# schematic_full.net
KiCad netlist of a schematic drawn in EAGLE
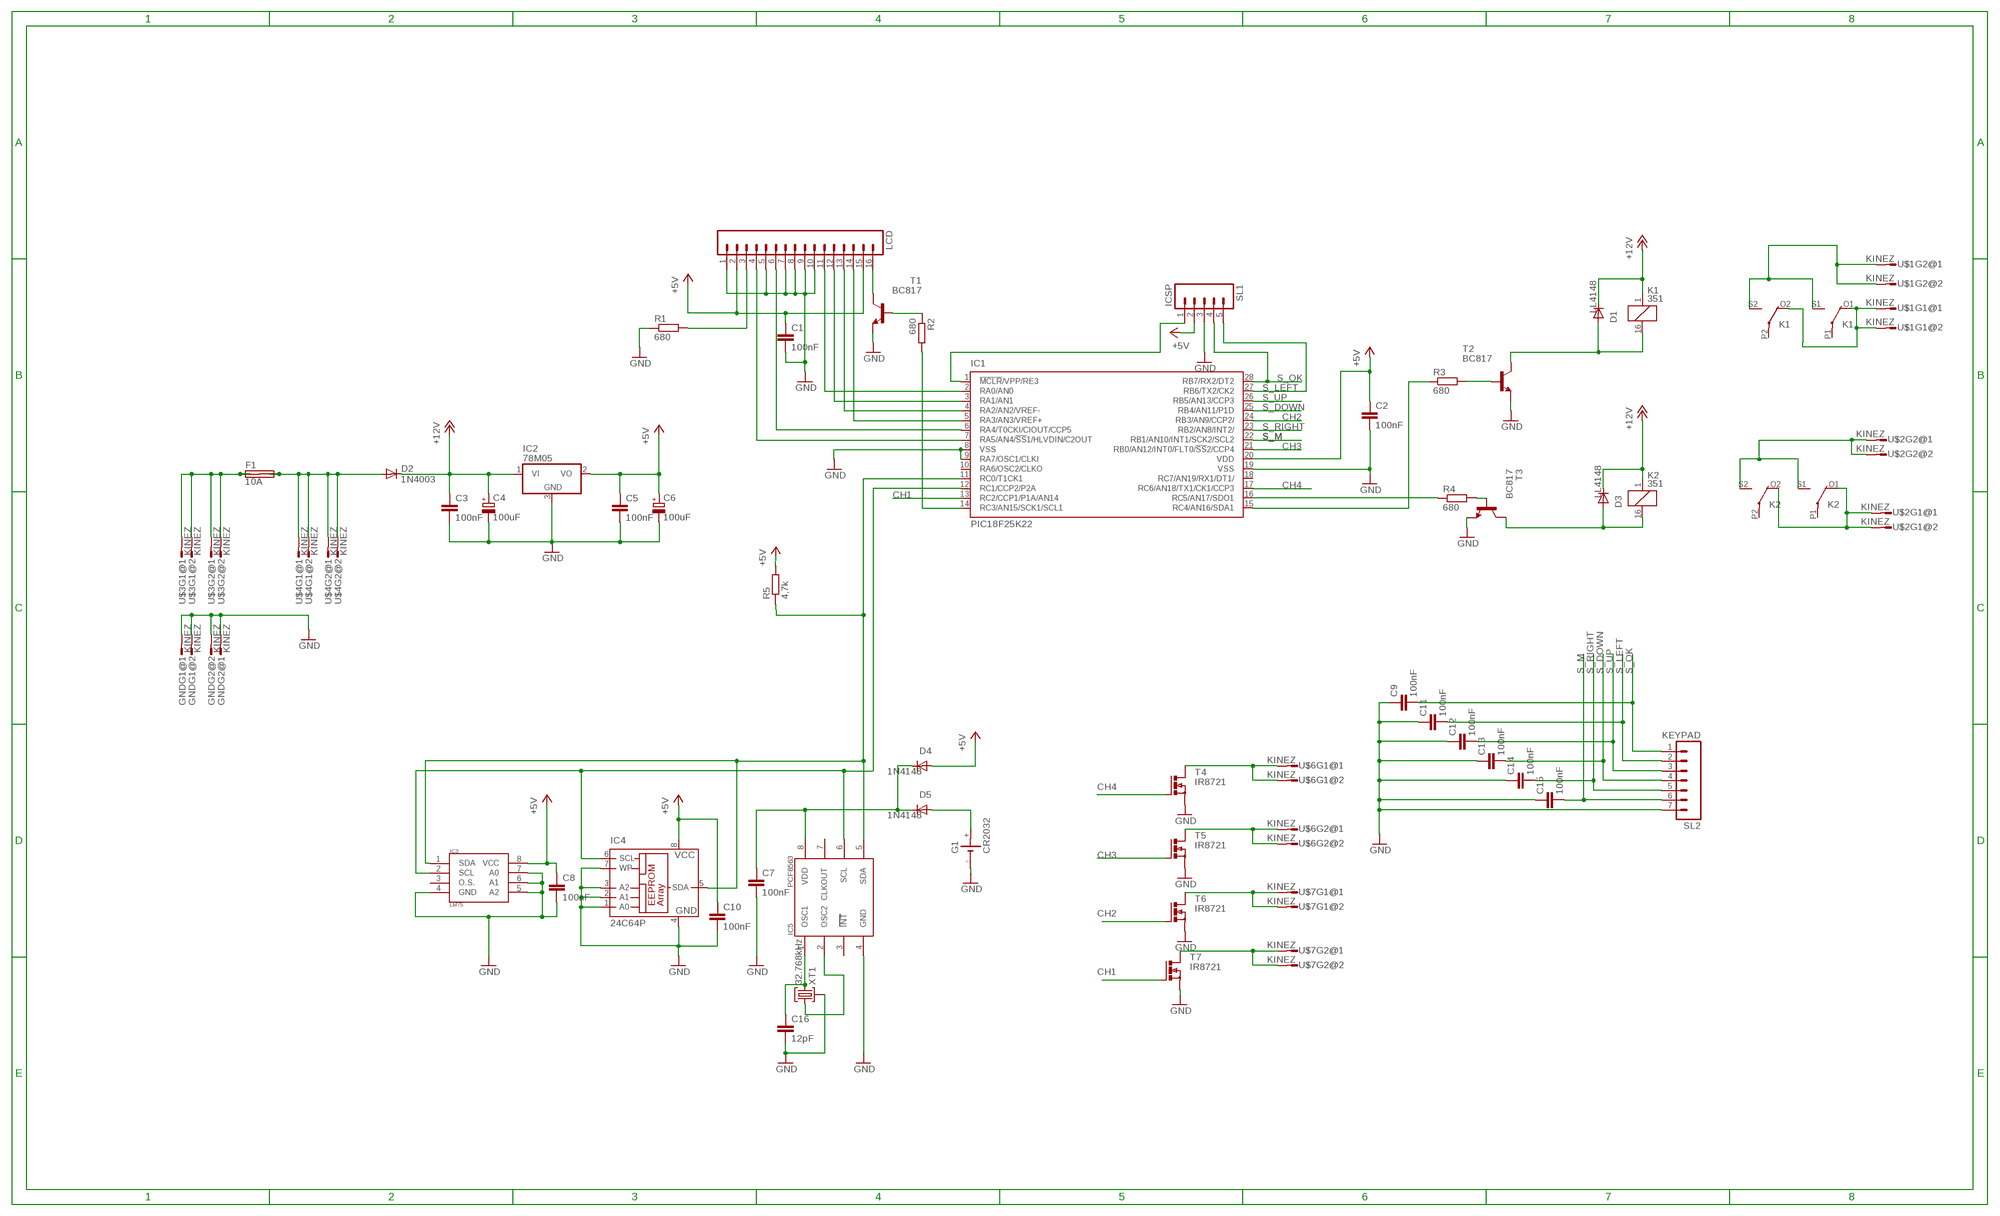
[diagram p0: schematic, sheet 1]

(export (version "E")
  (design (tool "Eeschema 10.0.6"))
  (components
    (comp (ref "C1")
      (value "100nF")
      (footprint "eagle-import:C0805K")
      (libsource (lib "eagle-import") (part "C-EUC0805K"))
    )
    (comp (ref "C2")
      (value "100nF")
      (footprint "eagle-import:C0805K")
      (libsource (lib "eagle-import") (part "C-EUC0805K"))
    )
    (comp (ref "C3")
      (value "100nF")
      (footprint "eagle-import:C0805K")
      (libsource (lib "eagle-import") (part "C-EUC0805K"))
    )
    (comp (ref "C4")
      (value "100uF")
      (footprint "eagle-import:E2,5-6E")
      (libsource (lib "eagle-import") (part "CPOL-EUE2,5-6E"))
    )
    (comp (ref "C5")
      (value "100nF")
      (footprint "eagle-import:C0805K")
      (libsource (lib "eagle-import") (part "C-EUC0805K"))
    )
    (comp (ref "C6")
      (value "100uF")
      (footprint "eagle-import:E2,5-6")
      (libsource (lib "eagle-import") (part "CPOL-EUE2.5-6"))
    )
    (comp (ref "C7")
      (value "100nF")
      (footprint "eagle-import:C0805K")
      (libsource (lib "eagle-import") (part "C-EUC0805K"))
    )
    (comp (ref "C8")
      (value "100nF")
      (footprint "eagle-import:C0805K")
      (libsource (lib "eagle-import") (part "C-EUC0805K"))
    )
    (comp (ref "C9")
      (value "100nF")
      (footprint "eagle-import:C0805K")
      (libsource (lib "eagle-import") (part "C-EUC0805K"))
    )
    (comp (ref "C10")
      (value "100nF")
      (footprint "eagle-import:C0805K")
      (libsource (lib "eagle-import") (part "C-EUC0805K"))
    )
    (comp (ref "C11")
      (value "100nF")
      (footprint "eagle-import:C0805K")
      (libsource (lib "eagle-import") (part "C-EUC0805K"))
    )
    (comp (ref "C12")
      (value "100nF")
      (footprint "eagle-import:C0805K")
      (libsource (lib "eagle-import") (part "C-EUC0805K"))
    )
    (comp (ref "C13")
      (value "100nF")
      (footprint "eagle-import:C0805K")
      (libsource (lib "eagle-import") (part "C-EUC0805K"))
    )
    (comp (ref "C14")
      (value "100nF")
      (footprint "eagle-import:C0805K")
      (libsource (lib "eagle-import") (part "C-EUC0805K"))
    )
    (comp (ref "C15")
      (value "100nF")
      (footprint "eagle-import:C0805K")
      (libsource (lib "eagle-import") (part "C-EUC0805K"))
    )
    (comp (ref "C16")
      (value "12pF")
      (footprint "eagle-import:C0805K")
      (libsource (lib "eagle-import") (part "C-EUC0805K"))
    )
    (comp (ref "D1")
      (value "LL4148")
      (footprint "eagle-import:DO214BA")
      (libsource (lib "eagle-import") (part "DIODE-DO214BA"))
    )
    (comp (ref "D2")
      (value "1N4003")
      (footprint "eagle-import:DO41-10")
      (libsource (lib "eagle-import") (part "1N4933"))
    )
    (comp (ref "D3")
      (value "LL4148")
      (footprint "eagle-import:DO214BA")
      (libsource (lib "eagle-import") (part "DIODE-DO214BA"))
    )
    (comp (ref "D4")
      (value "1N4148")
      (footprint "eagle-import:DO214BA")
      (libsource (lib "eagle-import") (part "DIODE-DO214BA"))
    )
    (comp (ref "D5")
      (value "1N4148")
      (footprint "eagle-import:DO214BA")
      (libsource (lib "eagle-import") (part "DIODE-DO214BA"))
    )
    (comp (ref "F1")
      (value "10A")
      (footprint "eagle-import:SHK20L")
      (libsource (lib "eagle-import") (part "SHK20L"))
    )
    (comp (ref "G1")
      (value "CR2032")
      (footprint "eagle-import:CR2032")
      (libsource (lib "eagle-import") (part "CR2032"))
    )
    (comp (ref "GND")
      (value "KINEZ")
      (footprint "eagle-import:KINEZ")
      (libsource (lib "eagle-import") (part "KINEZ"))
    )
    (comp (ref "IC1")
      (value "PIC18F25K22")
      (footprint "eagle-import:SSOP28")
      (libsource (lib "eagle-import") (part "PIC18F25K22/SS-E"))
    )
    (comp (ref "IC2")
      (value "78M05")
      (footprint "eagle-import:TO252")
      (libsource (lib "eagle-import") (part "78DT05"))
    )
    (comp (ref "IC3")
      (value "LM75")
      (footprint "eagle-import:SO08")
      (libsource (lib "eagle-import") (part "LM75"))
    )
    (comp (ref "IC4")
      (value "24C64P")
      (footprint "eagle-import:DIL8")
      (libsource (lib "eagle-import") (part "24PC64"))
    )
    (comp (ref "IC5")
      (value "PCF8563")
      (footprint "eagle-import:SO08")
      (libsource (lib "eagle-import") (part "PCF8563"))
    )
    (comp (ref "K1")
      (value "351")
      (footprint "eagle-import:351")
      (libsource (lib "eagle-import") (part "351"))
    )
    (comp (ref "K2")
      (value "351")
      (footprint "eagle-import:351")
      (libsource (lib "eagle-import") (part "351"))
    )
    (comp (ref "LCD")
      (value "M16")
      (footprint "eagle-import:16P")
      (libsource (lib "eagle-import") (part "M16"))
    )
    (comp (ref "R1")
      (value "680")
      (footprint "eagle-import:M0805")
      (libsource (lib "eagle-import") (part "R-EU_M0805"))
    )
    (comp (ref "R2")
      (value "680")
      (footprint "eagle-import:M0805")
      (libsource (lib "eagle-import") (part "R-EU_M0805"))
    )
    (comp (ref "R3")
      (value "680")
      (footprint "eagle-import:M0805")
      (libsource (lib "eagle-import") (part "R-EU_M0805"))
    )
    (comp (ref "R4")
      (value "680")
      (footprint "eagle-import:M0805")
      (libsource (lib "eagle-import") (part "R-EU_M0805"))
    )
    (comp (ref "R5")
      (value "4,7k")
      (footprint "eagle-import:M0805")
      (libsource (lib "eagle-import") (part "R-EU_M0805"))
    )
    (comp (ref "SL1")
      (value "ICSP")
      (footprint "eagle-import:05P")
      (libsource (lib "eagle-import") (part "M05"))
    )
    (comp (ref "SL2")
      (value "KEYPAD")
      (footprint "eagle-import:07PA")
      (libsource (lib "eagle-import") (part "MA07"))
    )
    (comp (ref "T1")
      (value "BC817")
      (footprint "eagle-import:SOT23-BEC")
      (libsource (lib "eagle-import") (part "BC817SMD-40"))
    )
    (comp (ref "T2")
      (value "BC817")
      (footprint "eagle-import:SOT23-BEC")
      (libsource (lib "eagle-import") (part "BC817SMD-40"))
    )
    (comp (ref "T3")
      (value "BC817")
      (footprint "eagle-import:SOT23-BEC")
      (libsource (lib "eagle-import") (part "BC817SMD-40"))
    )
    (comp (ref "T4")
      (value "IR8721")
      (footprint "eagle-import:TO252")
      (libsource (lib "eagle-import") (part "IRLR120N"))
    )
    (comp (ref "T5")
      (value "IR8721")
      (footprint "eagle-import:TO252")
      (libsource (lib "eagle-import") (part "IRLR120N"))
    )
    (comp (ref "T6")
      (value "IR8721")
      (footprint "eagle-import:TO252")
      (libsource (lib "eagle-import") (part "IRLR120N"))
    )
    (comp (ref "T7")
      (value "IR8721")
      (footprint "eagle-import:TO252")
      (libsource (lib "eagle-import") (part "IRLR120N"))
    )
    (comp (ref "U$1")
      (value "KINEZ")
      (footprint "eagle-import:KINEZ")
      (libsource (lib "eagle-import") (part "KINEZ"))
    )
    (comp (ref "U$2")
      (value "KINEZ")
      (footprint "eagle-import:KINEZ")
      (libsource (lib "eagle-import") (part "KINEZ"))
    )
    (comp (ref "U$3")
      (value "KINEZ")
      (footprint "eagle-import:KINEZ")
      (libsource (lib "eagle-import") (part "KINEZ"))
    )
    (comp (ref "U$4")
      (value "KINEZ")
      (footprint "eagle-import:KINEZ")
      (libsource (lib "eagle-import") (part "KINEZ"))
    )
    (comp (ref "U$6")
      (value "KINEZ")
      (footprint "eagle-import:KINEZ")
      (libsource (lib "eagle-import") (part "KINEZ"))
    )
    (comp (ref "U$7")
      (value "KINEZ")
      (footprint "eagle-import:KINEZ")
      (libsource (lib "eagle-import") (part "KINEZ"))
    )
    (comp (ref "XT1")
      (value "32.768kHz")
      (footprint "eagle-import:XTMINI")
      (libsource (lib "eagle-import") (part "XTMINI"))
    )
  )
  (nets
    (net (code "1") (name "+5V") (class "Default")
      (node (ref "C1") (pin "1") (pinfunction "1_1") (pintype "passive"))
      (node (ref "C10") (pin "1") (pinfunction "1_1") (pintype "passive"))
      (node (ref "C2") (pin "1") (pinfunction "1_1") (pintype "passive"))
      (node (ref "C5") (pin "1") (pinfunction "1_1") (pintype "passive"))
      (node (ref "C6") (pin "+") (pinfunction "+_+") (pintype "passive"))
      (node (ref "C8") (pin "1") (pinfunction "1_1") (pintype "passive"))
      (node (ref "D4") (pin "A") (pinfunction "A_A") (pintype "passive"))
      (node (ref "IC1") (pin "20") (pinfunction "VDD_20") (pintype "power_in"))
      (node (ref "IC2") (pin "2") (pinfunction "VO_2") (pintype "passive"))
      (node (ref "IC3") (pin "8") (pinfunction "VCC_8") (pintype "bidirectional"))
      (node (ref "IC4") (pin "8") (pinfunction "VCC_8") (pintype "power_in"))
      (node (ref "LCD") (pin "15") (pinfunction "15_15") (pintype "passive"))
      (node (ref "LCD") (pin "2") (pinfunction "2_2") (pintype "passive"))
      (node (ref "R5") (pin "2") (pinfunction "2_2") (pintype "passive"))
      (node (ref "SL1") (pin "2") (pinfunction "2_2") (pintype "passive"))
    )
    (net (code "2") (name "+12V") (class "Default")
      (node (ref "C3") (pin "1") (pinfunction "1_1") (pintype "passive"))
      (node (ref "C4") (pin "+") (pinfunction "+_+") (pintype "passive"))
      (node (ref "D1") (pin "C") (pinfunction "C_C") (pintype "passive"))
      (node (ref "D2") (pin "C") (pinfunction "C_C") (pintype "passive"))
      (node (ref "D3") (pin "C") (pinfunction "C_C") (pintype "passive"))
      (node (ref "IC2") (pin "1") (pinfunction "VI_1") (pintype "input"))
      (node (ref "K1") (pin "1") (pinfunction "1_1") (pintype "passive"))
      (node (ref "K2") (pin "1") (pinfunction "1_1") (pintype "passive"))
    )
    (net (code "3") (name "/CH1") (class "Default")
      (node (ref "IC1") (pin "13") (pinfunction "RC2/CCP1/P1A/AN14_13") (pintype "bidirectional"))
      (node (ref "T7") (pin "1") (pinfunction "G_1") (pintype "passive"))
    )
    (net (code "4") (name "/CH2") (class "Default")
      (node (ref "IC1") (pin "24") (pinfunction "RB3/AN9/CCP2/_24") (pintype "bidirectional"))
      (node (ref "T6") (pin "1") (pinfunction "G_1") (pintype "passive"))
    )
    (net (code "5") (name "/CH3") (class "Default")
      (node (ref "IC1") (pin "21") (pinfunction "RB0/AN12/INT0/FLT0/~{SS}2/CCP4_21") (pintype "bidirectional"))
      (node (ref "T5") (pin "1") (pinfunction "G_1") (pintype "passive"))
    )
    (net (code "6") (name "/CH4") (class "Default")
      (node (ref "IC1") (pin "17") (pinfunction "RC6/AN18/TX1/CK1/CCP3_17") (pintype "bidirectional"))
      (node (ref "T4") (pin "1") (pinfunction "G_1") (pintype "passive"))
    )
    (net (code "7") (name "/S_DOWN") (class "Default")
      (node (ref "C13") (pin "2") (pinfunction "2_2") (pintype "passive"))
      (node (ref "IC1") (pin "25") (pinfunction "RB4/AN11/P1D_25") (pintype "bidirectional"))
      (node (ref "SL2") (pin "4") (pinfunction "4_4") (pintype "passive"))
    )
    (net (code "8") (name "/S_LEFT") (class "Default")
      (node (ref "C11") (pin "2") (pinfunction "2_2") (pintype "passive"))
      (node (ref "IC1") (pin "27") (pinfunction "RB6/TX2/CK2_27") (pintype "bidirectional"))
      (node (ref "SL1") (pin "5") (pinfunction "5_5") (pintype "passive"))
      (node (ref "SL2") (pin "2") (pinfunction "2_2") (pintype "passive"))
    )
    (net (code "9") (name "/S_M") (class "Default")
      (node (ref "C15") (pin "2") (pinfunction "2_2") (pintype "passive"))
      (node (ref "IC1") (pin "22") (pinfunction "RB1/AN10/INT1/SCK2/SCL2_22") (pintype "bidirectional"))
      (node (ref "SL2") (pin "6") (pinfunction "6_6") (pintype "passive"))
    )
    (net (code "10") (name "/S_OK") (class "Default")
      (node (ref "C9") (pin "2") (pinfunction "2_2") (pintype "passive"))
      (node (ref "IC1") (pin "28") (pinfunction "RB7/RX2/DT2_28") (pintype "bidirectional"))
      (node (ref "SL1") (pin "4") (pinfunction "4_4") (pintype "passive"))
      (node (ref "SL2") (pin "1") (pinfunction "1_1") (pintype "passive"))
    )
    (net (code "11") (name "/S_RIGHT") (class "Default")
      (node (ref "C14") (pin "2") (pinfunction "2_2") (pintype "passive"))
      (node (ref "IC1") (pin "23") (pinfunction "RB2/AN8/INT2/_23") (pintype "bidirectional"))
      (node (ref "SL2") (pin "5") (pinfunction "5_5") (pintype "passive"))
    )
    (net (code "12") (name "/S_UP") (class "Default")
      (node (ref "C12") (pin "2") (pinfunction "2_2") (pintype "passive"))
      (node (ref "IC1") (pin "26") (pinfunction "RB5/AN13/CCP3_26") (pintype "bidirectional"))
      (node (ref "SL2") (pin "3") (pinfunction "3_3") (pintype "passive"))
    )
    (net (code "13") (name "GND") (class "Default")
      (node (ref "C1") (pin "2") (pinfunction "2_2") (pintype "passive"))
      (node (ref "C10") (pin "2") (pinfunction "2_2") (pintype "passive"))
      (node (ref "C11") (pin "1") (pinfunction "1_1") (pintype "passive"))
      (node (ref "C12") (pin "1") (pinfunction "1_1") (pintype "passive"))
      (node (ref "C13") (pin "1") (pinfunction "1_1") (pintype "passive"))
      (node (ref "C14") (pin "1") (pinfunction "1_1") (pintype "passive"))
      (node (ref "C15") (pin "1") (pinfunction "1_1") (pintype "passive"))
      (node (ref "C16") (pin "2") (pinfunction "2_2") (pintype "passive"))
      (node (ref "C2") (pin "2") (pinfunction "2_2") (pintype "passive"))
      (node (ref "C3") (pin "2") (pinfunction "2_2") (pintype "passive"))
      (node (ref "C4") (pin "-") (pinfunction "-_-") (pintype "passive"))
      (node (ref "C5") (pin "2") (pinfunction "2_2") (pintype "passive"))
      (node (ref "C6") (pin "-") (pinfunction "-_-") (pintype "passive"))
      (node (ref "C7") (pin "2") (pinfunction "2_2") (pintype "passive"))
      (node (ref "C8") (pin "2") (pinfunction "2_2") (pintype "passive"))
      (node (ref "C9") (pin "1") (pinfunction "1_1") (pintype "passive"))
      (node (ref "G1") (pin "-") (pinfunction "-_-") (pintype "passive"))
      (node (ref "GND") (pin "1") (pinfunction "S_1") (pintype "passive"))
      (node (ref "GND") (pin "2") (pinfunction "S_2") (pintype "passive"))
      (node (ref "GND") (pin "3") (pinfunction "S_3") (pintype "passive"))
      (node (ref "GND") (pin "4") (pinfunction "S_4") (pintype "passive"))
      (node (ref "IC1") (pin "19") (pinfunction "VSS_19") (pintype "power_in"))
      (node (ref "IC1") (pin "8") (pinfunction "VSS_8") (pintype "power_in"))
      (node (ref "IC1") (pin "9") (pinfunction "RA7/OSC1/CLKI_9") (pintype "input"))
      (node (ref "IC2") (pin "3") (pinfunction "GND_3") (pintype "passive"))
      (node (ref "IC3") (pin "4") (pinfunction "GND_4") (pintype "bidirectional"))
      (node (ref "IC3") (pin "5") (pinfunction "A2_5") (pintype "bidirectional"))
      (node (ref "IC3") (pin "6") (pinfunction "A1_6") (pintype "bidirectional"))
      (node (ref "IC3") (pin "7") (pinfunction "A0_7") (pintype "bidirectional"))
      (node (ref "IC4") (pin "1") (pinfunction "A0_1") (pintype "input"))
      (node (ref "IC4") (pin "2") (pinfunction "A1_2") (pintype "input"))
      (node (ref "IC4") (pin "3") (pinfunction "A2_3") (pintype "input"))
      (node (ref "IC4") (pin "4") (pinfunction "GND_4") (pintype "power_in"))
      (node (ref "IC4") (pin "7") (pinfunction "WP_7") (pintype "input"))
      (node (ref "IC5") (pin "4") (pinfunction "GND_4") (pintype "bidirectional"))
      (node (ref "LCD") (pin "1") (pinfunction "1_1") (pintype "passive"))
      (node (ref "LCD") (pin "10") (pinfunction "10_10") (pintype "passive"))
      (node (ref "LCD") (pin "5") (pinfunction "5_5") (pintype "passive"))
      (node (ref "LCD") (pin "7") (pinfunction "7_7") (pintype "passive"))
      (node (ref "LCD") (pin "8") (pinfunction "8_8") (pintype "passive"))
      (node (ref "LCD") (pin "9") (pinfunction "9_9") (pintype "passive"))
      (node (ref "R1") (pin "1") (pinfunction "1_1") (pintype "passive"))
      (node (ref "SL1") (pin "3") (pinfunction "3_3") (pintype "passive"))
      (node (ref "SL2") (pin "7") (pinfunction "7_7") (pintype "passive"))
      (node (ref "T1") (pin "E") (pinfunction "E_E") (pintype "passive"))
      (node (ref "T2") (pin "E") (pinfunction "E_E") (pintype "passive"))
      (node (ref "T3") (pin "E") (pinfunction "E_E") (pintype "passive"))
      (node (ref "T4") (pin "3") (pinfunction "S_3") (pintype "passive"))
      (node (ref "T5") (pin "3") (pinfunction "S_3") (pintype "passive"))
      (node (ref "T6") (pin "3") (pinfunction "S_3") (pintype "passive"))
      (node (ref "T7") (pin "3") (pinfunction "S_3") (pintype "passive"))
      (node (ref "XT1") (pin "P$3") (pinfunction "3_P$3") (pintype "passive"))
    )
    (net (code "14") (name "Net-(D5-PadA)") (class "Default")
      (node (ref "D5") (pin "A") (pinfunction "A_A") (pintype "passive"))
      (node (ref "G1") (pin "+") (pinfunction "+_+") (pintype "passive"))
    )
    (net (code "15") (name "Net-(IC1-RA0{slash}AN0)") (class "Default")
      (node (ref "IC1") (pin "2") (pinfunction "RA0/AN0_2") (pintype "bidirectional"))
      (node (ref "LCD") (pin "11") (pinfunction "11_11") (pintype "passive"))
    )
    (net (code "16") (name "Net-(IC1-RA1{slash}AN1)") (class "Default")
      (node (ref "IC1") (pin "3") (pinfunction "RA1/AN1_3") (pintype "bidirectional"))
      (node (ref "LCD") (pin "12") (pinfunction "12_12") (pintype "passive"))
    )
    (net (code "17") (name "Net-(IC1-RA2{slash}AN2{slash}VREF-)") (class "Default")
      (node (ref "IC1") (pin "4") (pinfunction "RA2/AN2/VREF-_4") (pintype "bidirectional"))
      (node (ref "LCD") (pin "13") (pinfunction "13_13") (pintype "passive"))
    )
    (net (code "18") (name "Net-(IC1-RA3{slash}AN3{slash}VREF+)") (class "Default")
      (node (ref "IC1") (pin "5") (pinfunction "RA3/AN3/VREF+_5") (pintype "bidirectional"))
      (node (ref "LCD") (pin "14") (pinfunction "14_14") (pintype "passive"))
    )
    (net (code "19") (name "Net-(IC1-RA4{slash}T0CKI{slash}CIOUT{slash}CCP5)") (class "Default")
      (node (ref "IC1") (pin "6") (pinfunction "RA4/T0CKI/CIOUT/CCP5_6") (pintype "bidirectional"))
      (node (ref "LCD") (pin "6") (pinfunction "6_6") (pintype "passive"))
    )
    (net (code "20") (name "Net-(IC1-RA5{slash}AN4{slash}~{SS}1{slash}HLVDIN{slash}C2OUT)") (class "Default")
      (node (ref "IC1") (pin "7") (pinfunction "RA5/AN4/~{SS}1/HLVDIN/C2OUT_7") (pintype "bidirectional"))
      (node (ref "LCD") (pin "4") (pinfunction "4_4") (pintype "passive"))
    )
    (net (code "21") (name "Net-(IC1-RC0{slash}T1CK1)") (class "Default")
      (node (ref "IC1") (pin "11") (pinfunction "RC0/T1CK1_11") (pintype "bidirectional"))
      (node (ref "IC3") (pin "1") (pinfunction "SDA_1") (pintype "bidirectional"))
      (node (ref "IC4") (pin "5") (pinfunction "SDA_5") (pintype "bidirectional"))
      (node (ref "IC5") (pin "5") (pinfunction "SDA_5") (pintype "bidirectional"))
      (node (ref "R5") (pin "1") (pinfunction "1_1") (pintype "passive"))
    )
    (net (code "22") (name "Net-(IC1-RC1{slash}CCP2{slash}P2A)") (class "Default")
      (node (ref "IC1") (pin "12") (pinfunction "RC1/CCP2/P2A_12") (pintype "bidirectional"))
      (node (ref "IC3") (pin "2") (pinfunction "SCL_2") (pintype "bidirectional"))
      (node (ref "IC4") (pin "6") (pinfunction "SCL_6") (pintype "input"))
      (node (ref "IC5") (pin "6") (pinfunction "SCL_6") (pintype "bidirectional"))
    )
    (net (code "23") (name "Net-(IC1-RC3{slash}AN15{slash}SCK1{slash}SCL1)") (class "Default")
      (node (ref "IC1") (pin "14") (pinfunction "RC3/AN15/SCK1/SCL1_14") (pintype "bidirectional"))
      (node (ref "R2") (pin "2") (pinfunction "2_2") (pintype "passive"))
    )
    (net (code "24") (name "Net-(IC1-RC4{slash}AN16{slash}SDA1)") (class "Default")
      (node (ref "IC1") (pin "15") (pinfunction "RC4/AN16/SDA1_15") (pintype "bidirectional"))
      (node (ref "R3") (pin "1") (pinfunction "1_1") (pintype "passive"))
    )
    (net (code "25") (name "Net-(IC1-RC5{slash}AN17{slash}SDO1)") (class "Default")
      (node (ref "IC1") (pin "16") (pinfunction "RC5/AN17/SDO1_16") (pintype "bidirectional"))
      (node (ref "R4") (pin "1") (pinfunction "1_1") (pintype "passive"))
    )
    (net (code "26") (name "Net-(IC1-~{MCLR}{slash}VPP{slash}RE3)") (class "Default")
      (node (ref "IC1") (pin "1") (pinfunction "~{MCLR}/VPP/RE3_1") (pintype "input"))
      (node (ref "SL1") (pin "1") (pinfunction "1_1") (pintype "passive"))
    )
    (net (code "27") (name "Net-(IC5-OSC1)") (class "Default")
      (node (ref "C16") (pin "1") (pinfunction "1_1") (pintype "passive"))
      (node (ref "IC5") (pin "1") (pinfunction "OSC1_1") (pintype "bidirectional"))
      (node (ref "XT1") (pin "P$2") (pinfunction "2_P$2") (pintype "passive"))
    )
    (net (code "28") (name "Net-(IC5-OSC2)") (class "Default")
      (node (ref "IC5") (pin "2") (pinfunction "OSC2_2") (pintype "bidirectional"))
      (node (ref "XT1") (pin "P$1") (pinfunction "1_P$1") (pintype "passive"))
    )
    (net (code "29") (name "Net-(IC5-VDD)") (class "Default")
      (node (ref "C7") (pin "1") (pinfunction "1_1") (pintype "passive"))
      (node (ref "D4") (pin "C") (pinfunction "C_C") (pintype "passive"))
      (node (ref "D5") (pin "C") (pinfunction "C_C") (pintype "passive"))
      (node (ref "IC5") (pin "8") (pinfunction "VDD_8") (pintype "bidirectional"))
    )
    (net (code "30") (name "Net-(K1A-2)") (class "Default")
      (node (ref "D1") (pin "A") (pinfunction "A_A") (pintype "passive"))
      (node (ref "K1") (pin "16") (pinfunction "2_16") (pintype "passive"))
      (node (ref "T2") (pin "C") (pinfunction "C_C") (pintype "passive"))
    )
    (net (code "31") (name "Net-(K1B-O)") (class "Default")
      (node (ref "K1") (pin "O1") (pinfunction "O_O1") (pintype "passive"))
      (node (ref "K1") (pin "O2") (pinfunction "O_O2") (pintype "passive"))
      (node (ref "U$1") (pin "1") (pinfunction "S_1") (pintype "passive"))
      (node (ref "U$1") (pin "2") (pinfunction "S_2") (pintype "passive"))
    )
    (net (code "32") (name "Net-(K1B-S)") (class "Default")
      (node (ref "K1") (pin "S1") (pinfunction "S_S1") (pintype "passive"))
      (node (ref "K1") (pin "S2") (pinfunction "S_S2") (pintype "passive"))
      (node (ref "U$1") (pin "3") (pinfunction "S_3") (pintype "passive"))
      (node (ref "U$1") (pin "4") (pinfunction "S_4") (pintype "passive"))
    )
    (net (code "33") (name "Net-(K2A-2)") (class "Default")
      (node (ref "D3") (pin "A") (pinfunction "A_A") (pintype "passive"))
      (node (ref "K2") (pin "16") (pinfunction "2_16") (pintype "passive"))
      (node (ref "T3") (pin "C") (pinfunction "C_C") (pintype "passive"))
    )
    (net (code "34") (name "Net-(K2B-O)") (class "Default")
      (node (ref "K2") (pin "O1") (pinfunction "O_O1") (pintype "passive"))
      (node (ref "K2") (pin "O2") (pinfunction "O_O2") (pintype "passive"))
      (node (ref "U$2") (pin "1") (pinfunction "S_1") (pintype "passive"))
      (node (ref "U$2") (pin "2") (pinfunction "S_2") (pintype "passive"))
    )
    (net (code "35") (name "Net-(K2B-S)") (class "Default")
      (node (ref "K2") (pin "S1") (pinfunction "S_S1") (pintype "passive"))
      (node (ref "K2") (pin "S2") (pinfunction "S_S2") (pintype "passive"))
      (node (ref "U$2") (pin "3") (pinfunction "S_3") (pintype "passive"))
      (node (ref "U$2") (pin "4") (pinfunction "S_4") (pintype "passive"))
    )
    (net (code "36") (name "Net-(LCD-Pad3)") (class "Default")
      (node (ref "LCD") (pin "3") (pinfunction "3_3") (pintype "passive"))
      (node (ref "R1") (pin "2") (pinfunction "2_2") (pintype "passive"))
    )
    (net (code "37") (name "Net-(LCD-Pad16)") (class "Default")
      (node (ref "LCD") (pin "16") (pinfunction "16_16") (pintype "passive"))
      (node (ref "T1") (pin "C") (pinfunction "C_C") (pintype "passive"))
    )
    (net (code "38") (name "Net-(R2-Pad1)") (class "Default")
      (node (ref "R2") (pin "1") (pinfunction "1_1") (pintype "passive"))
      (node (ref "T1") (pin "B") (pinfunction "B_B") (pintype "passive"))
    )
    (net (code "39") (name "Net-(R3-Pad2)") (class "Default")
      (node (ref "R3") (pin "2") (pinfunction "2_2") (pintype "passive"))
      (node (ref "T2") (pin "B") (pinfunction "B_B") (pintype "passive"))
    )
    (net (code "40") (name "Net-(R4-Pad2)") (class "Default")
      (node (ref "R4") (pin "2") (pinfunction "2_2") (pintype "passive"))
      (node (ref "T3") (pin "B") (pinfunction "B_B") (pintype "passive"))
    )
    (net (code "41") (name "Net-(T4-D)") (class "Default")
      (node (ref "T4") (pin "2") (pinfunction "D_2") (pintype "passive"))
      (node (ref "U$6") (pin "1") (pinfunction "S_1") (pintype "passive"))
      (node (ref "U$6") (pin "2") (pinfunction "S_2") (pintype "passive"))
    )
    (net (code "42") (name "Net-(T5-D)") (class "Default")
      (node (ref "T5") (pin "2") (pinfunction "D_2") (pintype "passive"))
      (node (ref "U$6") (pin "3") (pinfunction "S_3") (pintype "passive"))
      (node (ref "U$6") (pin "4") (pinfunction "S_4") (pintype "passive"))
    )
    (net (code "43") (name "Net-(T6-D)") (class "Default")
      (node (ref "T6") (pin "2") (pinfunction "D_2") (pintype "passive"))
      (node (ref "U$7") (pin "1") (pinfunction "S_1") (pintype "passive"))
      (node (ref "U$7") (pin "2") (pinfunction "S_2") (pintype "passive"))
    )
    (net (code "44") (name "Net-(T7-D)") (class "Default")
      (node (ref "T7") (pin "2") (pinfunction "D_2") (pintype "passive"))
      (node (ref "U$7") (pin "3") (pinfunction "S_3") (pintype "passive"))
      (node (ref "U$7") (pin "4") (pinfunction "S_4") (pintype "passive"))
    )
    (net (code "45") (name "Net-(U$3A-S)") (class "Default")
      (node (ref "F1") (pin "1A") (pinfunction "1A_1A") (pintype "passive"))
      (node (ref "F1") (pin "1B") (pinfunction "1B_1B") (pintype "passive"))
      (node (ref "U$3") (pin "1") (pinfunction "S_1") (pintype "passive"))
      (node (ref "U$3") (pin "2") (pinfunction "S_2") (pintype "passive"))
      (node (ref "U$3") (pin "3") (pinfunction "S_3") (pintype "passive"))
      (node (ref "U$3") (pin "4") (pinfunction "S_4") (pintype "passive"))
    )
    (net (code "46") (name "Net-(U$4A-S)") (class "Default")
      (node (ref "D2") (pin "A") (pinfunction "A_A") (pintype "passive"))
      (node (ref "F1") (pin "2A") (pinfunction "2A_2A") (pintype "passive"))
      (node (ref "F1") (pin "2B") (pinfunction "2B_2B") (pintype "passive"))
      (node (ref "U$4") (pin "1") (pinfunction "S_1") (pintype "passive"))
      (node (ref "U$4") (pin "2") (pinfunction "S_2") (pintype "passive"))
      (node (ref "U$4") (pin "3") (pinfunction "S_3") (pintype "passive"))
      (node (ref "U$4") (pin "4") (pinfunction "S_4") (pintype "passive"))
    )
    (net (code "47") (name "unconnected-(IC1-RA6{slash}OSC2{slash}CLKO-Pad10)") (class "Default")
      (node (ref "IC1") (pin "10") (pinfunction "RA6/OSC2/CLKO_10") (pintype "output"))
    )
    (net (code "48") (name "unconnected-(IC1-RC7{slash}AN19{slash}RX1{slash}DT1{slash}-Pad18)") (class "Default")
      (node (ref "IC1") (pin "18") (pinfunction "RC7/AN19/RX1/DT1/_18") (pintype "bidirectional"))
    )
    (net (code "49") (name "unconnected-(IC3-O.S.-Pad3)") (class "Default")
      (node (ref "IC3") (pin "3") (pinfunction "O.S._3") (pintype "bidirectional"))
    )
    (net (code "50") (name "unconnected-(IC5-CLKOUT-Pad7)") (class "Default")
      (node (ref "IC5") (pin "7") (pinfunction "CLKOUT_7") (pintype "bidirectional"))
    )
    (net (code "51") (name "unconnected-(IC5-INT-Pad3)") (class "Default")
      (node (ref "IC5") (pin "3") (pinfunction "INT_3") (pintype "bidirectional"))
    )
    (net (code "52") (name "unconnected-(K1B-P-PadP1)") (class "Default")
      (node (ref "K1") (pin "P1") (pinfunction "P_P1") (pintype "passive"))
    )
    (net (code "53") (name "unconnected-(K1C-P-PadP2)") (class "Default")
      (node (ref "K1") (pin "P2") (pinfunction "P_P2") (pintype "passive"))
    )
    (net (code "54") (name "unconnected-(K2B-P-PadP1)") (class "Default")
      (node (ref "K2") (pin "P1") (pinfunction "P_P1") (pintype "passive"))
    )
    (net (code "55") (name "unconnected-(K2C-P-PadP2)") (class "Default")
      (node (ref "K2") (pin "P2") (pinfunction "P_P2") (pintype "passive"))
    )
  )
)
